# IO2.net
KiCad netlist of a schematic drawn in Altium Designer
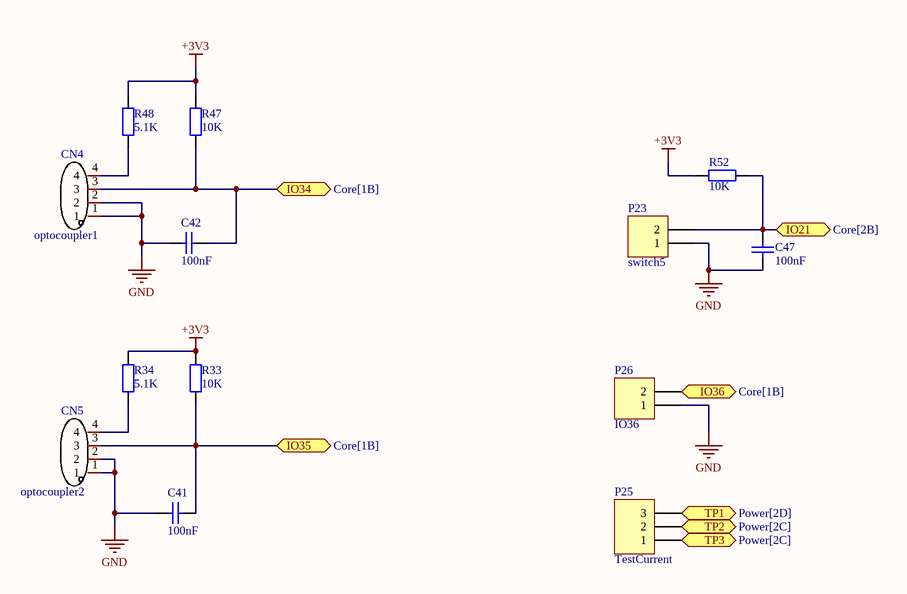
[diagram p0: IO2.SchDoc]

(export (version "E")
  (design (tool "Eeschema 10.0.6"))
  (components
    (comp (ref "C41")
      (value "100nF")
      (footprint "6-0805_N")
      (description "Capacitor")
      (fields (field (name "Comment") "Cap") (field (name "PUBLISHER") "Altium Limited"))
      (libsource (lib "Miscellaneous Devices") (part "Cap"))
    )
    (comp (ref "C42")
      (value "100nF")
      (footprint "6-0805_N")
      (description "Capacitor")
      (fields (field (name "Comment") "Cap") (field (name "PUBLISHER") "Altium Limited"))
      (libsource (lib "Miscellaneous Devices") (part "Cap"))
    )
    (comp (ref "C47")
      (value "100nF")
      (footprint "6-0805_N")
      (description "Capacitor")
      (fields (field (name "Comment") "Cap") (field (name "PUBLISHER") "Altium Limited"))
      (libsource (lib "Miscellaneous Devices") (part "Cap"))
    )
    (comp (ref "CN4")
      (value "ZX-XH2.54-4PZZ")
      (footprint "CONN-TH_4P-P2.50_4PIN")
      (fields (field (name "MANUFACTURER") "Megastar(兆星)") (field (name "NAME") "optocoupler1"))
      (libsource (lib "4PZZ") (part "ZX-XH2.54-4PZZ"))
    )
    (comp (ref "CN5")
      (value "ZX-XH2.54-4PZZ")
      (footprint "CONN-TH_4P-P2.50_4PIN")
      (fields (field (name "MANUFACTURER") "Megastar(兆星)") (field (name "NAME") "optocoupler2"))
      (libsource (lib "4PZZ") (part "ZX-XH2.54-4PZZ"))
    )
    (comp (ref "P23")
      (value "switch5")
      (footprint "HDR1X2")
      (description "Header, 2-Pin")
      (fields (field (name "PUBLISHER") "Altium Limited"))
      (libsource (lib "Miscellaneous Connectors") (part "Header 2"))
    )
    (comp (ref "P25")
      (value "TestCurrent")
      (footprint "HDR1X3")
      (description "Header, 3-Pin")
      (fields (field (name "PUBLISHER") "Altium Limited"))
      (libsource (lib "Miscellaneous Connectors") (part "Header 3"))
    )
    (comp (ref "P26")
      (value "IO36")
      (footprint "HDR1X2")
      (description "Header, 2-Pin")
      (fields (field (name "PUBLISHER") "Altium Limited"))
      (libsource (lib "Miscellaneous Connectors") (part "Header 2"))
    )
    (comp (ref "R33")
      (value "10K")
      (footprint "6-0805_N")
      (description "Resistor")
      (fields (field (name "Comment") "Res2") (field (name "PUBLISHER") "Altium Limited"))
      (libsource (lib "Miscellaneous Devices") (part "Res2"))
    )
    (comp (ref "R34")
      (value "5.1K")
      (footprint "6-0805_N")
      (description "Resistor")
      (fields (field (name "Comment") "Res2") (field (name "PUBLISHER") "Altium Limited"))
      (libsource (lib "Miscellaneous Devices") (part "Res2"))
    )
    (comp (ref "R47")
      (value "10K")
      (footprint "6-0805_N")
      (description "Resistor")
      (fields (field (name "Comment") "Res2") (field (name "PUBLISHER") "Altium Limited"))
      (libsource (lib "") (part "Res2_1"))
    )
    (comp (ref "R48")
      (value "5.1K")
      (footprint "6-0805_N")
      (description "Resistor")
      (fields (field (name "Comment") "Res2") (field (name "PUBLISHER") "Altium Limited"))
      (libsource (lib "") (part "Res2_1"))
    )
    (comp (ref "R52")
      (value "10K")
      (footprint "6-0805_N")
      (description "Resistor")
      (fields (field (name "Comment") "Res2") (field (name "PUBLISHER") "Altium Limited"))
      (libsource (lib "") (part "Res2_2"))
    )
  )
  (nets
    (net (code "1") (name "+3V3") (class "Default")
      (node (ref "R33") (pin "2") (pinfunction "2_2") (pintype "passive"))
      (node (ref "R34") (pin "2") (pinfunction "2_2") (pintype "passive"))
      (node (ref "R47") (pin "1") (pinfunction "1_1") (pintype "passive"))
      (node (ref "R48") (pin "1") (pinfunction "1_1") (pintype "passive"))
      (node (ref "R52") (pin "1") (pinfunction "1_1") (pintype "passive"))
    )
    (net (code "2") (name "/IO21") (class "Default")
      (node (ref "C47") (pin "2") (pinfunction "2_2") (pintype "passive"))
      (node (ref "P23") (pin "2") (pinfunction "2_2") (pintype "passive"))
      (node (ref "R52") (pin "2") (pinfunction "2_2") (pintype "passive"))
    )
    (net (code "3") (name "/IO34") (class "Default")
      (node (ref "C42") (pin "1") (pinfunction "1_1") (pintype "passive"))
      (node (ref "CN4") (pin "3") (pinfunction "3_3") (pintype "passive"))
      (node (ref "R47") (pin "2") (pinfunction "2_2") (pintype "passive"))
    )
    (net (code "4") (name "/IO35") (class "Default")
      (node (ref "C41") (pin "1") (pinfunction "1_1") (pintype "passive"))
      (node (ref "CN5") (pin "3") (pinfunction "3_3") (pintype "passive"))
      (node (ref "R33") (pin "1") (pinfunction "1_1") (pintype "passive"))
    )
    (net (code "5") (name "/IO36") (class "Default")
      (node (ref "P26") (pin "2") (pinfunction "2_2") (pintype "passive"))
    )
    (net (code "6") (name "/TP1") (class "Default")
      (node (ref "P25") (pin "3") (pinfunction "3_3") (pintype "passive"))
    )
    (net (code "7") (name "/TP2") (class "Default")
      (node (ref "P25") (pin "2") (pinfunction "2_2") (pintype "passive"))
    )
    (net (code "8") (name "/TP3") (class "Default")
      (node (ref "P25") (pin "1") (pinfunction "1_1") (pintype "passive"))
    )
    (net (code "9") (name "GND") (class "Default")
      (node (ref "C41") (pin "2") (pinfunction "2_2") (pintype "passive"))
      (node (ref "C42") (pin "2") (pinfunction "2_2") (pintype "passive"))
      (node (ref "C47") (pin "1") (pinfunction "1_1") (pintype "passive"))
      (node (ref "CN4") (pin "1") (pinfunction "1_1") (pintype "passive"))
      (node (ref "CN4") (pin "2") (pinfunction "2_2") (pintype "passive"))
      (node (ref "CN5") (pin "1") (pinfunction "1_1") (pintype "passive"))
      (node (ref "CN5") (pin "2") (pinfunction "2_2") (pintype "passive"))
      (node (ref "P23") (pin "1") (pinfunction "1_1") (pintype "passive"))
      (node (ref "P26") (pin "1") (pinfunction "1_1") (pintype "passive"))
    )
    (net (code "10") (name "Net-(CN4-Pad4)") (class "Default")
      (node (ref "CN4") (pin "4") (pinfunction "4_4") (pintype "passive"))
      (node (ref "R48") (pin "2") (pinfunction "2_2") (pintype "passive"))
    )
    (net (code "11") (name "Net-(CN5-Pad4)") (class "Default")
      (node (ref "CN5") (pin "4") (pinfunction "4_4") (pintype "passive"))
      (node (ref "R34") (pin "1") (pinfunction "1_1") (pintype "passive"))
    )
  )
)
